# IC_Schematic.net
KiCad netlist of a schematic drawn in Altium Designer
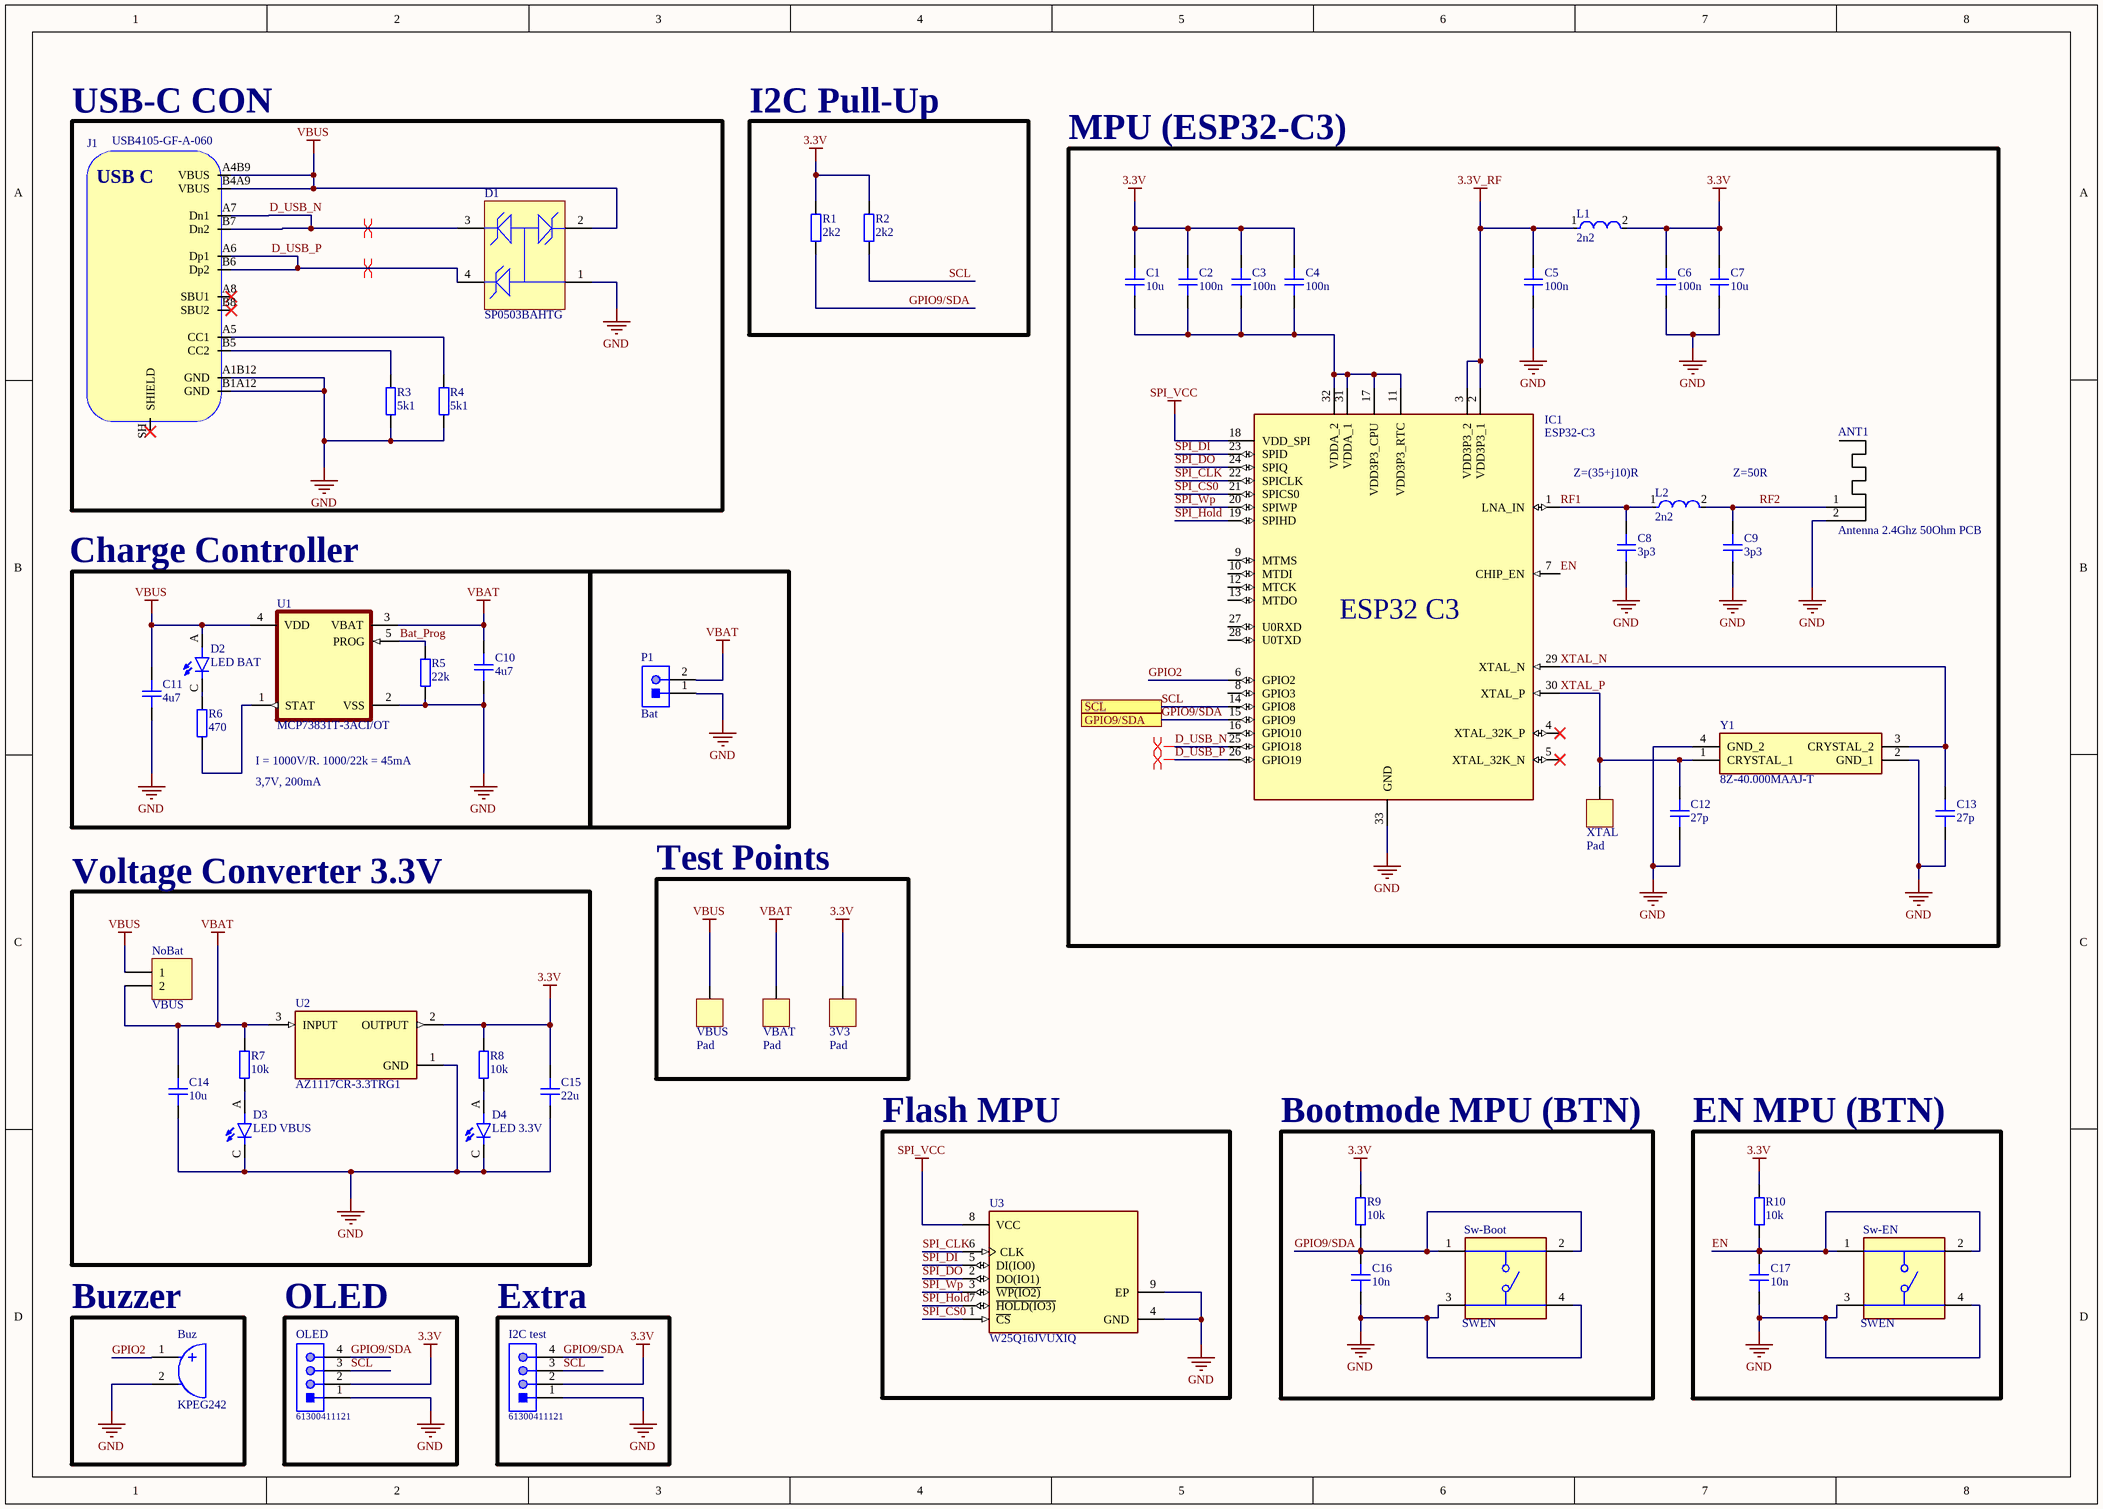
[diagram p0: IC_Schematic.SchDoc]

(export (version "E")
  (design (tool "Eeschema 10.0.6"))
  (components
    (comp (ref "3V3")
      (value "Pad")
      (footprint "PAD_SQ_2MM")
      (description "Test Point Square 2mm")
      (libsource (lib "Schem_Lib_DaanHeetkamp.") (part "PAD_SQ_2MM"))
    )
    (comp (ref "ANT1")
      (value "Antenna 2.4Ghz 50Ohm PCB")
      (footprint "PCB_Antenna_2.4GHz_50Ohm")
      (description "ESP32 C3")
      (libsource (lib "Schem_Lib_DaanHeetkamp.") (part "Antenna 2.4Ghz 50Ohm PCB"))
    )
    (comp (ref "Buz")
      (value "KPEG242")
      (footprint "KINGS-KPEG242-2")
      (description "Piezo Indicator, 4100 Hz, 3 to 16 V, -20 to 70 degC, 2-Pin THD, RoHS")
      (fields (field (name "PARTNUMBER") "KPE-242") (field (name "MANUFACTURER") "KingstateElectronicsCorp."))
      (libsource (lib "Altium Content Vault") (part "KINGS-KPEG242-2"))
    )
    (comp (ref "C1")
      (value "10u")
      (footprint "CAP_1206")
      (description "Capacitor SMD 1206 50V")
      (libsource (lib "Schem_Lib_DaanHeetkamp.") (part "CAP_1206_50V"))
    )
    (comp (ref "C2")
      (value "100n")
      (footprint "CAP_1206")
      (description "Capacitor SMD 1206 50V")
      (libsource (lib "Schem_Lib_DaanHeetkamp.") (part "CAP_1206_50V"))
    )
    (comp (ref "C3")
      (value "100n")
      (footprint "CAP_1206")
      (description "Capacitor SMD 1206 50V")
      (libsource (lib "Schem_Lib_DaanHeetkamp.") (part "CAP_1206_50V"))
    )
    (comp (ref "C4")
      (value "100n")
      (footprint "CAP_1206")
      (description "Capacitor SMD 1206 50V")
      (libsource (lib "Schem_Lib_DaanHeetkamp.") (part "CAP_1206_50V"))
    )
    (comp (ref "C5")
      (value "100n")
      (footprint "CAP_1206")
      (description "Capacitor SMD 1206 50V")
      (libsource (lib "Schem_Lib_DaanHeetkamp.") (part "CAP_1206_50V"))
    )
    (comp (ref "C6")
      (value "100n")
      (footprint "CAP_1206")
      (description "Capacitor SMD 1206 50V")
      (libsource (lib "Schem_Lib_DaanHeetkamp.") (part "CAP_1206_50V"))
    )
    (comp (ref "C7")
      (value "10u")
      (footprint "CAP_1206")
      (description "Capacitor SMD 1206 50V")
      (libsource (lib "Schem_Lib_DaanHeetkamp.") (part "CAP_1206_50V"))
    )
    (comp (ref "C8")
      (value "3p3")
      (footprint "CAP_1206")
      (description "Capacitor SMD 1206 50V")
      (libsource (lib "Schem_Lib_DaanHeetkamp.") (part "CAP_1206_50V"))
    )
    (comp (ref "C9")
      (value "3p3")
      (footprint "CAP_1206")
      (description "Capacitor SMD 1206 50V")
      (libsource (lib "Schem_Lib_DaanHeetkamp.") (part "CAP_1206_50V"))
    )
    (comp (ref "C10")
      (value "4u7")
      (footprint "CAP_1206")
      (description "Capacitor SMD 1206 50V")
      (libsource (lib "Schem_Lib_DaanHeetkamp.") (part "CAP_1206_50V"))
    )
    (comp (ref "C11")
      (value "4u7")
      (footprint "CAP_1206")
      (description "Capacitor SMD 1206 50V")
      (libsource (lib "Schem_Lib_DaanHeetkamp.") (part "CAP_1206_50V"))
    )
    (comp (ref "C12")
      (value "27p")
      (footprint "CAP_1206")
      (description "Capacitor SMD 1206 50V")
      (libsource (lib "Schem_Lib_DaanHeetkamp.") (part "CAP_1206_50V"))
    )
    (comp (ref "C13")
      (value "27p")
      (footprint "CAP_1206")
      (description "Capacitor SMD 1206 50V")
      (libsource (lib "Schem_Lib_DaanHeetkamp.") (part "CAP_1206_50V"))
    )
    (comp (ref "C14")
      (value "10u")
      (footprint "CAP_1206")
      (description "Capacitor SMD 1206 50V")
      (libsource (lib "Schem_Lib_DaanHeetkamp.") (part "CAP_1206_50V"))
    )
    (comp (ref "C15")
      (value "22u")
      (footprint "CAP_1206")
      (description "Capacitor SMD 1206 50V")
      (libsource (lib "Schem_Lib_DaanHeetkamp.") (part "CAP_1206_50V"))
    )
    (comp (ref "C16")
      (value "10n")
      (footprint "CAP_1206")
      (description "Capacitor SMD 1206 50V")
      (libsource (lib "Schem_Lib_DaanHeetkamp.") (part "CAP_1206_50V"))
    )
    (comp (ref "C17")
      (value "10n")
      (footprint "CAP_1206")
      (description "Capacitor SMD 1206 50V")
      (libsource (lib "Schem_Lib_DaanHeetkamp.") (part "CAP_1206_50V"))
    )
    (comp (ref "D1")
      (value "SP0503BAHTG")
      (footprint "LFUS-SOT143-4_V")
      (description "TVS Diode Array, 30 pF, 30 KV, -40 to 85 degC, 4-Pin SOT143, RoHS, Tape and Reel")
      (fields (field (name "MANUFACTURER") "Littelfuse"))
      (libsource (lib "Altium Content Vault") (part "LFUS-SP0503BAHTG-SOT143-4"))
    )
    (comp (ref "D2")
      (value "LED BAT")
      (footprint "PCB_Lib_DaanHeetkamp:LED_1206")
      (description "Yellow 587nm LED Indication - Discrete 2V 1206 _3216 Metric_")
      (fields (field (name "MF") "Lite-On Inc.") (field (name "MP") "LTST-C230KSKT"))
      (libsource (lib "Schem_Lib_DaanHeetkamp.") (part "LED - 1206"))
    )
    (comp (ref "D3")
      (value "LED VBUS")
      (footprint "PCB_Lib_DaanHeetkamp:LED_1206")
      (description "Yellow 587nm LED Indication - Discrete 2V 1206 _3216 Metric_")
      (fields (field (name "MF") "Lite-On Inc.") (field (name "MP") "LTST-C230KSKT"))
      (libsource (lib "Schem_Lib_DaanHeetkamp.") (part "LED - 1206"))
    )
    (comp (ref "D4")
      (value "LED 3.3V")
      (footprint "PCB_Lib_DaanHeetkamp:LED_1206")
      (description "Yellow 587nm LED Indication - Discrete 2V 1206 _3216 Metric_")
      (fields (field (name "MF") "Lite-On Inc.") (field (name "MP") "LTST-C230KSKT"))
      (libsource (lib "Schem_Lib_DaanHeetkamp.") (part "LED - 1206"))
    )
    (comp (ref "I2C test")
      (value "61300411121")
      (footprint "61300411121")
      (description "THT Vertical Pin Header WR-PHD, Pitch 2.54 mm, Single Row, 4 pins")
      (fields (field (name "MANUFACTURER") "Wurth Elektronik") (field (name "PUBLISHER") "WurthElektronik"))
      (libsource (lib "Altium Content Vault") (part "WE-CN-1P-M-R4"))
    )
    (comp (ref "IC1")
      (value "ESP32-C3")
      (footprint "PCB_Lib_DaanHeetkamp:QFN50P500X500X90-33N-D")
      (description "Integrated Circuit")
      (fields (field (name "MOUSER PART NUMBER") "356-ESP32-C3"))
      (libsource (lib "Schem_Lib_DaanHeetkamp.") (part "ESP32-C3"))
    )
    (comp (ref "J1")
      (value "USB4105-GF-A-060")
      (footprint "USB4105-GF-A-060")
      (description "USB Connector Type C SMT 12 Pin")
      (fields (field (name "MANUFACTURER") "GCT"))
      (libsource (lib "Schem_Lib_DaanHeetkamp.") (part "USB4105-GF-A-060"))
    )
    (comp (ref "L1")
      (value "2n2")
      (footprint "FP-LQW18AN_10-MFG")
      (description "Wire Wound RF Inductor for Automotive 2.2nH ±0.5nH 1400mA 0.018Ω 0603 (1608)")
      (libsource (lib "Altium Content Vault") (part "725321dda6339637d4d059423bc1c3c"))
    )
    (comp (ref "L2")
      (value "2n2")
      (footprint "FP-LQW18AN_10-MFG")
      (description "Wire Wound RF Inductor for Automotive 2.2nH ±0.5nH 1400mA 0.018Ω 0603 (1608)")
      (libsource (lib "Altium Content Vault") (part "725321dda6339637d4d059423bc1c3c"))
    )
    (comp (ref "NoBat")
      (value "VBUS")
      (footprint "MHDR1X2")
      (description "Header, 2-Pin")
      (fields (field (name "PUBLISHER") "Altium Limited"))
      (libsource (lib "Miscellaneous Connectors") (part "MHDR1X2"))
    )
    (comp (ref "OLED")
      (value "61300411121")
      (footprint "61300411121")
      (description "THT Vertical Pin Header WR-PHD, Pitch 2.54 mm, Single Row, 4 pins")
      (fields (field (name "MANUFACTURER") "Wurth Elektronik") (field (name "PUBLISHER") "WurthElektronik"))
      (libsource (lib "Altium Content Vault") (part "WE-CN-1P-M-R4"))
    )
    (comp (ref "P1")
      (value "Bat")
      (footprint "JST-S2B-PH-K-S_V")
      (fields (field (name "TOLERANCE") "20%"))
      (libsource (lib "Altium Content Vault") (part "CN-1P-M-R2"))
    )
    (comp (ref "R1")
      (value "2k2")
      (footprint "RES_1206")
      (description "Resistor SMD 1206")
      (libsource (lib "Schem_Lib_DaanHeetkamp.") (part "RES_1206"))
    )
    (comp (ref "R2")
      (value "2k2")
      (footprint "RES_1206")
      (description "Resistor SMD 1206")
      (libsource (lib "Schem_Lib_DaanHeetkamp.") (part "RES_1206"))
    )
    (comp (ref "R3")
      (value "5k1")
      (footprint "RES_1206")
      (description "Resistor SMD 1206")
      (libsource (lib "Schem_Lib_DaanHeetkamp.") (part "RES_1206"))
    )
    (comp (ref "R4")
      (value "5k1")
      (footprint "RES_1206")
      (description "Resistor SMD 1206")
      (libsource (lib "Schem_Lib_DaanHeetkamp.") (part "RES_1206"))
    )
    (comp (ref "R5")
      (value "22k")
      (footprint "RES_1206")
      (description "Resistor SMD 1206")
      (libsource (lib "Schem_Lib_DaanHeetkamp.") (part "RES_1206"))
    )
    (comp (ref "R6")
      (value "470")
      (footprint "RES_1206")
      (description "Resistor SMD 1206")
      (libsource (lib "Schem_Lib_DaanHeetkamp.") (part "RES_1206"))
    )
    (comp (ref "R7")
      (value "10k")
      (footprint "RES_1206")
      (description "Resistor SMD 1206")
      (libsource (lib "Schem_Lib_DaanHeetkamp.") (part "RES_1206"))
    )
    (comp (ref "R8")
      (value "10k")
      (footprint "RES_1206")
      (description "Resistor SMD 1206")
      (libsource (lib "Schem_Lib_DaanHeetkamp.") (part "RES_1206"))
    )
    (comp (ref "R9")
      (value "10k")
      (footprint "RES_1206")
      (description "Resistor SMD 1206")
      (libsource (lib "Schem_Lib_DaanHeetkamp.") (part "RES_1206"))
    )
    (comp (ref "R10")
      (value "10k")
      (footprint "RES_1206")
      (description "Resistor SMD 1206")
      (libsource (lib "Schem_Lib_DaanHeetkamp.") (part "RES_1206"))
    )
    (comp (ref "Sw-Boot")
      (value "SWEN")
      (footprint "Switch/Button 4 Pin Through Hole")
      (fields (field (name "MP") "TS02-66-120-BK-260-LCR-D") (field (name "MF") "CUI Devices"))
      (libsource (lib "Schem_Lib_DaanHeetkamp") (part "Switch/Button 4 Pin Through Hole"))
    )
    (comp (ref "Sw-EN")
      (value "SWEN")
      (footprint "Switch/Button 4 Pin Through Hole")
      (fields (field (name "MP") "TS02-66-120-BK-260-LCR-D") (field (name "MF") "CUI Devices"))
      (libsource (lib "Schem_Lib_DaanHeetkamp") (part "Switch/Button 4 Pin Through Hole"))
    )
    (comp (ref "U1")
      (value "MCP73831T-3ACI/OT")
      (footprint "PCB_Lib_DaanHeetkamp:SOT95P270X145-5N")
      (description "Charger IC Lithium Ion/Polymer SOT-23-5")
      (fields (field (name "MF") "Microchip"))
      (libsource (lib "Schem_Lib_DaanHeetkamp") (part "MCP73831T-3ACI/OT"))
    )
    (comp (ref "U2")
      (value "AZ1117CR-3.3TRG1")
      (footprint "FP-SOT89-MFG")
      (description "IC REG LINEAR 3.3V 800MA SOT89")
      (fields
        (field (name "OCTOPART") "https://octopart.com/az1117cr-3.3trg1-diodes+inc.-30954805")
        (field (name "MANUFACTURER") "Diodes Inc.")
      )
      (libsource (lib "Altium Content Vault") (part "80dc4d5e0c5bf011f486f511683fde3"))
    )
    (comp (ref "U3")
      (value "W25Q16JVUXIQ")
      (footprint "FP-UX-MFG")
      (description "IC FLASH 16MBIT SPI/QUAD 8USON")
      (libsource (lib "Altium Content Vault") (part "ef7e6bbff5b18f94b0c5acc221a373e"))
    )
    (comp (ref "VBAT")
      (value "Pad")
      (footprint "PAD_SQ_2MM")
      (description "Test Point Square 2mm")
      (libsource (lib "Schem_Lib_DaanHeetkamp.") (part "PAD_SQ_2MM"))
    )
    (comp (ref "VBUS")
      (value "Pad")
      (footprint "PAD_SQ_2MM")
      (description "Test Point Square 2mm")
      (libsource (lib "Schem_Lib_DaanHeetkamp.") (part "PAD_SQ_2MM"))
    )
    (comp (ref "XTAL")
      (value "Pad")
      (footprint "PAD_SQ_2MM")
      (description "Test Point Square 2mm")
      (libsource (lib "Schem_Lib_DaanHeetkamp.") (part "PAD_SQ_2MM"))
    )
    (comp (ref "Y1")
      (value "8Z-40.000MAAJ-T")
      (footprint "PCB_Lib_DaanHeetkamp:8Z40000MAAJT")
      (description "Crystal or Oscillator")
      (libsource (lib "Schem_Lib_DaanHeetkamp.") (part "8Z-40.000MAAJ-T"))
    )
  )
  (nets
    (net (code "1") (name "/Bat_Prog") (class "Default")
      (node (ref "R5") (pin "2") (pinfunction "2_2") (pintype "passive"))
      (node (ref "U1") (pin "5") (pinfunction "PROG_5") (pintype "input"))
    )
    (net (code "2") (name "/D_USB_N") (class "Default")
      (node (ref "D1") (pin "3") (pinfunction "3_3") (pintype "passive"))
      (node (ref "IC1") (pin "25") (pinfunction "GPIO18_25") (pintype "bidirectional"))
      (node (ref "J1") (pin "A7") (pinfunction "Dn1_A7") (pintype "passive"))
      (node (ref "J1") (pin "B7") (pinfunction "Dn2_B7") (pintype "passive"))
    )
    (net (code "3") (name "/D_USB_P") (class "Default")
      (node (ref "D1") (pin "4") (pinfunction "4_4") (pintype "passive"))
      (node (ref "IC1") (pin "26") (pinfunction "GPIO19_26") (pintype "bidirectional"))
      (node (ref "J1") (pin "A6") (pinfunction "Dp1_A6") (pintype "passive"))
      (node (ref "J1") (pin "B6") (pinfunction "Dp2_B6") (pintype "passive"))
    )
    (net (code "4") (name "/EN") (class "Default")
      (node (ref "C17") (pin "2") (pinfunction "2_2") (pintype "passive"))
      (node (ref "IC1") (pin "7") (pinfunction "CHIP_EN_7") (pintype "input"))
      (node (ref "R10") (pin "2") (pinfunction "2_2") (pintype "passive"))
      (node (ref "Sw-EN") (pin "1") (pinfunction "1_1") (pintype "passive"))
      (node (ref "Sw-EN") (pin "2") (pinfunction "2_2") (pintype "passive"))
    )
    (net (code "5") (name "/GPIO2") (class "Default")
      (node (ref "Buz") (pin "1") (pinfunction "1_1") (pintype "passive"))
      (node (ref "IC1") (pin "6") (pinfunction "GPIO2_6") (pintype "bidirectional"))
    )
    (net (code "6") (name "/GPIO9{slash}SDA") (class "Default")
      (node (ref "C16") (pin "2") (pinfunction "2_2") (pintype "passive"))
      (node (ref "I2C test") (pin "4") (pinfunction "4_4") (pintype "passive"))
      (node (ref "IC1") (pin "15") (pinfunction "GPIO9_15") (pintype "bidirectional"))
      (node (ref "OLED") (pin "4") (pinfunction "4_4") (pintype "passive"))
      (node (ref "R1") (pin "2") (pinfunction "2_2") (pintype "passive"))
      (node (ref "R9") (pin "2") (pinfunction "2_2") (pintype "passive"))
      (node (ref "Sw-Boot") (pin "1") (pinfunction "1_1") (pintype "passive"))
      (node (ref "Sw-Boot") (pin "2") (pinfunction "2_2") (pintype "passive"))
    )
    (net (code "7") (name "/RF1") (class "Default")
      (node (ref "C8") (pin "2") (pinfunction "2_2") (pintype "passive"))
      (node (ref "IC1") (pin "1") (pinfunction "LNA_IN_1") (pintype "bidirectional"))
      (node (ref "L2") (pin "1") (pinfunction "1_1") (pintype "passive"))
    )
    (net (code "8") (name "/RF2") (class "Default")
      (node (ref "ANT1") (pin "1") (pinfunction "RF_1") (pintype "passive"))
      (node (ref "C9") (pin "2") (pinfunction "2_2") (pintype "passive"))
      (node (ref "L2") (pin "2") (pinfunction "2_2") (pintype "passive"))
    )
    (net (code "9") (name "/SCL") (class "Default")
      (node (ref "I2C test") (pin "3") (pinfunction "3_3") (pintype "passive"))
      (node (ref "IC1") (pin "14") (pinfunction "GPIO8_14") (pintype "bidirectional"))
      (node (ref "OLED") (pin "3") (pinfunction "3_3") (pintype "passive"))
      (node (ref "R2") (pin "2") (pinfunction "2_2") (pintype "passive"))
    )
    (net (code "10") (name "/SPI_CLK") (class "Default")
      (node (ref "IC1") (pin "22") (pinfunction "SPICLK_22") (pintype "bidirectional"))
      (node (ref "U3") (pin "6") (pinfunction "CLK_6") (pintype "input"))
    )
    (net (code "11") (name "/SPI_CS0") (class "Default")
      (node (ref "IC1") (pin "21") (pinfunction "SPICS0_21") (pintype "bidirectional"))
      (node (ref "U3") (pin "1") (pinfunction "~{CS}_1") (pintype "input"))
    )
    (net (code "12") (name "/SPI_DI") (class "Default")
      (node (ref "IC1") (pin "23") (pinfunction "SPID_23") (pintype "bidirectional"))
      (node (ref "U3") (pin "5") (pinfunction "DI(IO0)_5") (pintype "bidirectional"))
    )
    (net (code "13") (name "/SPI_DO") (class "Default")
      (node (ref "IC1") (pin "24") (pinfunction "SPIQ_24") (pintype "bidirectional"))
      (node (ref "U3") (pin "2") (pinfunction "DO(IO1)_2") (pintype "bidirectional"))
    )
    (net (code "14") (name "/SPI_Hold") (class "Default")
      (node (ref "IC1") (pin "19") (pinfunction "SPIHD_19") (pintype "bidirectional"))
      (node (ref "U3") (pin "7") (pinfunction "~{HOLD(IO3)}_7") (pintype "bidirectional"))
    )
    (net (code "15") (name "/SPI_Wp") (class "Default")
      (node (ref "IC1") (pin "20") (pinfunction "SPIWP_20") (pintype "bidirectional"))
      (node (ref "U3") (pin "3") (pinfunction "~{WP(IO2)}_3") (pintype "bidirectional"))
    )
    (net (code "16") (name "/XTAL_N") (class "Default")
      (node (ref "C13") (pin "2") (pinfunction "2_2") (pintype "passive"))
      (node (ref "IC1") (pin "29") (pinfunction "XTAL_N_29") (pintype "input"))
      (node (ref "Y1") (pin "3") (pinfunction "CRYSTAL_2_3") (pintype "passive"))
    )
    (net (code "17") (name "/XTAL_P") (class "Default")
      (node (ref "C12") (pin "2") (pinfunction "2_2") (pintype "passive"))
      (node (ref "IC1") (pin "30") (pinfunction "XTAL_P_30") (pintype "input"))
      (node (ref "XTAL") (pin "1") (pinfunction "1_1") (pintype "passive"))
      (node (ref "Y1") (pin "1") (pinfunction "CRYSTAL_1_1") (pintype "passive"))
    )
    (net (code "18") (name "3.3V") (class "Default")
      (node (ref "3V3") (pin "1") (pinfunction "1_1") (pintype "passive"))
      (node (ref "C1") (pin "2") (pinfunction "2_2") (pintype "passive"))
      (node (ref "C15") (pin "2") (pinfunction "2_2") (pintype "passive"))
      (node (ref "C2") (pin "2") (pinfunction "2_2") (pintype "passive"))
      (node (ref "C3") (pin "2") (pinfunction "2_2") (pintype "passive"))
      (node (ref "C4") (pin "2") (pinfunction "2_2") (pintype "passive"))
      (node (ref "C6") (pin "2") (pinfunction "2_2") (pintype "passive"))
      (node (ref "C7") (pin "2") (pinfunction "2_2") (pintype "passive"))
      (node (ref "I2C test") (pin "2") (pinfunction "2_2") (pintype "passive"))
      (node (ref "L1") (pin "2") (pinfunction "2_2") (pintype "passive"))
      (node (ref "OLED") (pin "2") (pinfunction "2_2") (pintype "passive"))
      (node (ref "R1") (pin "1") (pinfunction "1_1") (pintype "passive"))
      (node (ref "R10") (pin "1") (pinfunction "1_1") (pintype "passive"))
      (node (ref "R2") (pin "1") (pinfunction "1_1") (pintype "passive"))
      (node (ref "R8") (pin "2") (pinfunction "2_2") (pintype "passive"))
      (node (ref "R9") (pin "1") (pinfunction "1_1") (pintype "passive"))
      (node (ref "U2") (pin "2") (pinfunction "OUTPUT_2") (pintype "output"))
    )
    (net (code "19") (name "3.3V_RF") (class "Default")
      (node (ref "C5") (pin "2") (pinfunction "2_2") (pintype "passive"))
      (node (ref "IC1") (pin "2") (pinfunction "VDD3P3_1_2") (pintype "passive"))
      (node (ref "IC1") (pin "3") (pinfunction "VDD3P3_2_3") (pintype "passive"))
      (node (ref "L1") (pin "1") (pinfunction "1_1") (pintype "passive"))
    )
    (net (code "20") (name "GND") (class "Default")
      (node (ref "ANT1") (pin "2") (pinfunction "GND_2") (pintype "passive"))
      (node (ref "Buz") (pin "2") (pinfunction "2_2") (pintype "passive"))
      (node (ref "C10") (pin "1") (pinfunction "1_1") (pintype "passive"))
      (node (ref "C11") (pin "1") (pinfunction "1_1") (pintype "passive"))
      (node (ref "C12") (pin "1") (pinfunction "1_1") (pintype "passive"))
      (node (ref "C13") (pin "1") (pinfunction "1_1") (pintype "passive"))
      (node (ref "C14") (pin "1") (pinfunction "1_1") (pintype "passive"))
      (node (ref "C15") (pin "1") (pinfunction "1_1") (pintype "passive"))
      (node (ref "C16") (pin "1") (pinfunction "1_1") (pintype "passive"))
      (node (ref "C17") (pin "1") (pinfunction "1_1") (pintype "passive"))
      (node (ref "C5") (pin "1") (pinfunction "1_1") (pintype "passive"))
      (node (ref "C6") (pin "1") (pinfunction "1_1") (pintype "passive"))
      (node (ref "C7") (pin "1") (pinfunction "1_1") (pintype "passive"))
      (node (ref "C8") (pin "1") (pinfunction "1_1") (pintype "passive"))
      (node (ref "C9") (pin "1") (pinfunction "1_1") (pintype "passive"))
      (node (ref "D1") (pin "1") (pinfunction "1_1") (pintype "passive"))
      (node (ref "D3") (pin "C") (pinfunction "C_C") (pintype "passive"))
      (node (ref "D4") (pin "C") (pinfunction "C_C") (pintype "passive"))
      (node (ref "I2C test") (pin "1") (pinfunction "1_1") (pintype "passive"))
      (node (ref "IC1") (pin "33") (pinfunction "GND_33") (pintype "passive"))
      (node (ref "J1") (pin "A1B12") (pinfunction "GND_A1B12") (pintype "passive"))
      (node (ref "J1") (pin "B1A12") (pinfunction "GND_B1A12") (pintype "passive"))
      (node (ref "OLED") (pin "1") (pinfunction "1_1") (pintype "passive"))
      (node (ref "P1") (pin "1") (pinfunction "1_1") (pintype "passive"))
      (node (ref "R3") (pin "1") (pinfunction "1_1") (pintype "passive"))
      (node (ref "R4") (pin "1") (pinfunction "1_1") (pintype "passive"))
      (node (ref "R5") (pin "1") (pinfunction "1_1") (pintype "passive"))
      (node (ref "Sw-Boot") (pin "3") (pinfunction "3_3") (pintype "passive"))
      (node (ref "Sw-Boot") (pin "4") (pinfunction "4_4") (pintype "passive"))
      (node (ref "Sw-EN") (pin "3") (pinfunction "3_3") (pintype "passive"))
      (node (ref "Sw-EN") (pin "4") (pinfunction "4_4") (pintype "passive"))
      (node (ref "U1") (pin "2") (pinfunction "VSS_2") (pintype "power_in"))
      (node (ref "U2") (pin "1") (pinfunction "GND_1") (pintype "power_in"))
      (node (ref "U3") (pin "4") (pinfunction "GND_4") (pintype "power_in"))
      (node (ref "U3") (pin "9") (pinfunction "EP_9") (pintype "passive"))
      (node (ref "Y1") (pin "2") (pinfunction "GND_1_2") (pintype "passive"))
      (node (ref "Y1") (pin "4") (pinfunction "GND_2_4") (pintype "passive"))
    )
    (net (code "21") (name "Net-(D2-PadC)") (class "Default")
      (node (ref "D2") (pin "C") (pinfunction "C_C") (pintype "passive"))
      (node (ref "R6") (pin "2") (pinfunction "2_2") (pintype "passive"))
    )
    (net (code "22") (name "Net-(D3-PadA)") (class "Default")
      (node (ref "D3") (pin "A") (pinfunction "A_A") (pintype "passive"))
      (node (ref "R7") (pin "1") (pinfunction "1_1") (pintype "passive"))
    )
    (net (code "23") (name "Net-(D4-PadA)") (class "Default")
      (node (ref "D4") (pin "A") (pinfunction "A_A") (pintype "passive"))
      (node (ref "R8") (pin "1") (pinfunction "1_1") (pintype "passive"))
    )
    (net (code "24") (name "Net-(IC1-VDD3P3_CPU)") (class "Default")
      (node (ref "C1") (pin "1") (pinfunction "1_1") (pintype "passive"))
      (node (ref "C2") (pin "1") (pinfunction "1_1") (pintype "passive"))
      (node (ref "C3") (pin "1") (pinfunction "1_1") (pintype "passive"))
      (node (ref "C4") (pin "1") (pinfunction "1_1") (pintype "passive"))
      (node (ref "IC1") (pin "11") (pinfunction "VDD3P3_RTC_11") (pintype "passive"))
      (node (ref "IC1") (pin "17") (pinfunction "VDD3P3_CPU_17") (pintype "passive"))
      (node (ref "IC1") (pin "31") (pinfunction "VDDA_1_31") (pintype "passive"))
      (node (ref "IC1") (pin "32") (pinfunction "VDDA_2_32") (pintype "passive"))
    )
    (net (code "25") (name "Net-(J1-CC1)") (class "Default")
      (node (ref "J1") (pin "A5") (pinfunction "CC1_A5") (pintype "passive"))
      (node (ref "R4") (pin "2") (pinfunction "2_2") (pintype "passive"))
    )
    (net (code "26") (name "Net-(J1-CC2)") (class "Default")
      (node (ref "J1") (pin "B5") (pinfunction "CC2_B5") (pintype "passive"))
      (node (ref "R3") (pin "2") (pinfunction "2_2") (pintype "passive"))
    )
    (net (code "27") (name "Net-(U1-STAT)") (class "Default")
      (node (ref "R6") (pin "1") (pinfunction "1_1") (pintype "passive"))
      (node (ref "U1") (pin "1") (pinfunction "STAT_1") (pintype "output"))
    )
    (net (code "28") (name "SPI_VCC") (class "Default")
      (node (ref "IC1") (pin "18") (pinfunction "VDD_SPI_18") (pintype "passive"))
      (node (ref "U3") (pin "8") (pinfunction "VCC_8") (pintype "power_in"))
    )
    (net (code "29") (name "VBAT") (class "Default")
      (node (ref "C10") (pin "2") (pinfunction "2_2") (pintype "passive"))
      (node (ref "C14") (pin "2") (pinfunction "2_2") (pintype "passive"))
      (node (ref "NoBat") (pin "2") (pinfunction "2_2") (pintype "passive"))
      (node (ref "P1") (pin "2") (pinfunction "2_2") (pintype "passive"))
      (node (ref "R7") (pin "2") (pinfunction "2_2") (pintype "passive"))
      (node (ref "U1") (pin "3") (pinfunction "VBAT_3") (pintype "power_in"))
      (node (ref "U2") (pin "3") (pinfunction "INPUT_3") (pintype "input"))
      (node (ref "VBAT") (pin "1") (pinfunction "1_1") (pintype "passive"))
    )
    (net (code "30") (name "VBUS") (class "Default")
      (node (ref "C11") (pin "2") (pinfunction "2_2") (pintype "passive"))
      (node (ref "D1") (pin "2") (pinfunction "2_2") (pintype "passive"))
      (node (ref "D2") (pin "A") (pinfunction "A_A") (pintype "passive"))
      (node (ref "J1") (pin "A4B9") (pinfunction "VBUS_A4B9") (pintype "passive"))
      (node (ref "J1") (pin "B4A9") (pinfunction "VBUS_B4A9") (pintype "passive"))
      (node (ref "NoBat") (pin "1") (pinfunction "1_1") (pintype "passive"))
      (node (ref "U1") (pin "4") (pinfunction "VDD_4") (pintype "power_in"))
      (node (ref "VBUS") (pin "1") (pinfunction "1_1") (pintype "passive"))
    )
    (net (code "31") (name "unconnected-(IC1-GPIO3-Pad8)") (class "Default")
      (node (ref "IC1") (pin "8") (pinfunction "GPIO3_8") (pintype "bidirectional"))
    )
    (net (code "32") (name "unconnected-(IC1-GPIO10-Pad16)") (class "Default")
      (node (ref "IC1") (pin "16") (pinfunction "GPIO10_16") (pintype "bidirectional"))
    )
    (net (code "33") (name "unconnected-(IC1-MTCK-Pad12)") (class "Default")
      (node (ref "IC1") (pin "12") (pinfunction "MTCK_12") (pintype "bidirectional"))
    )
    (net (code "34") (name "unconnected-(IC1-MTDI-Pad10)") (class "Default")
      (node (ref "IC1") (pin "10") (pinfunction "MTDI_10") (pintype "bidirectional"))
    )
    (net (code "35") (name "unconnected-(IC1-MTDO-Pad13)") (class "Default")
      (node (ref "IC1") (pin "13") (pinfunction "MTDO_13") (pintype "bidirectional"))
    )
    (net (code "36") (name "unconnected-(IC1-MTMS-Pad9)") (class "Default")
      (node (ref "IC1") (pin "9") (pinfunction "MTMS_9") (pintype "bidirectional"))
    )
    (net (code "37") (name "unconnected-(IC1-U0RXD-Pad27)") (class "Default")
      (node (ref "IC1") (pin "27") (pinfunction "U0RXD_27") (pintype "bidirectional"))
    )
    (net (code "38") (name "unconnected-(IC1-U0TXD-Pad28)") (class "Default")
      (node (ref "IC1") (pin "28") (pinfunction "U0TXD_28") (pintype "bidirectional"))
    )
    (net (code "39") (name "unconnected-(IC1-XTAL_32K_N-Pad5)") (class "Default")
      (node (ref "IC1") (pin "5") (pinfunction "XTAL_32K_N_5") (pintype "bidirectional+no_connect"))
    )
    (net (code "40") (name "unconnected-(IC1-XTAL_32K_P-Pad4)") (class "Default")
      (node (ref "IC1") (pin "4") (pinfunction "XTAL_32K_P_4") (pintype "bidirectional+no_connect"))
    )
    (net (code "41") (name "unconnected-(J1-SBU1-PadA8)") (class "Default")
      (node (ref "J1") (pin "A8") (pinfunction "SBU1_A8") (pintype "passive+no_connect"))
    )
    (net (code "42") (name "unconnected-(J1-SBU2-PadB8)") (class "Default")
      (node (ref "J1") (pin "B8") (pinfunction "SBU2_B8") (pintype "passive+no_connect"))
    )
    (net (code "43") (name "unconnected-(J1-SHIELD-PadSH)") (class "Default")
      (node (ref "J1") (pin "SH") (pinfunction "SHIELD_SH") (pintype "passive+no_connect"))
    )
  )
)
